# Arduino-Pro-Mini.net
KiCad netlist of a schematic drawn in EAGLE
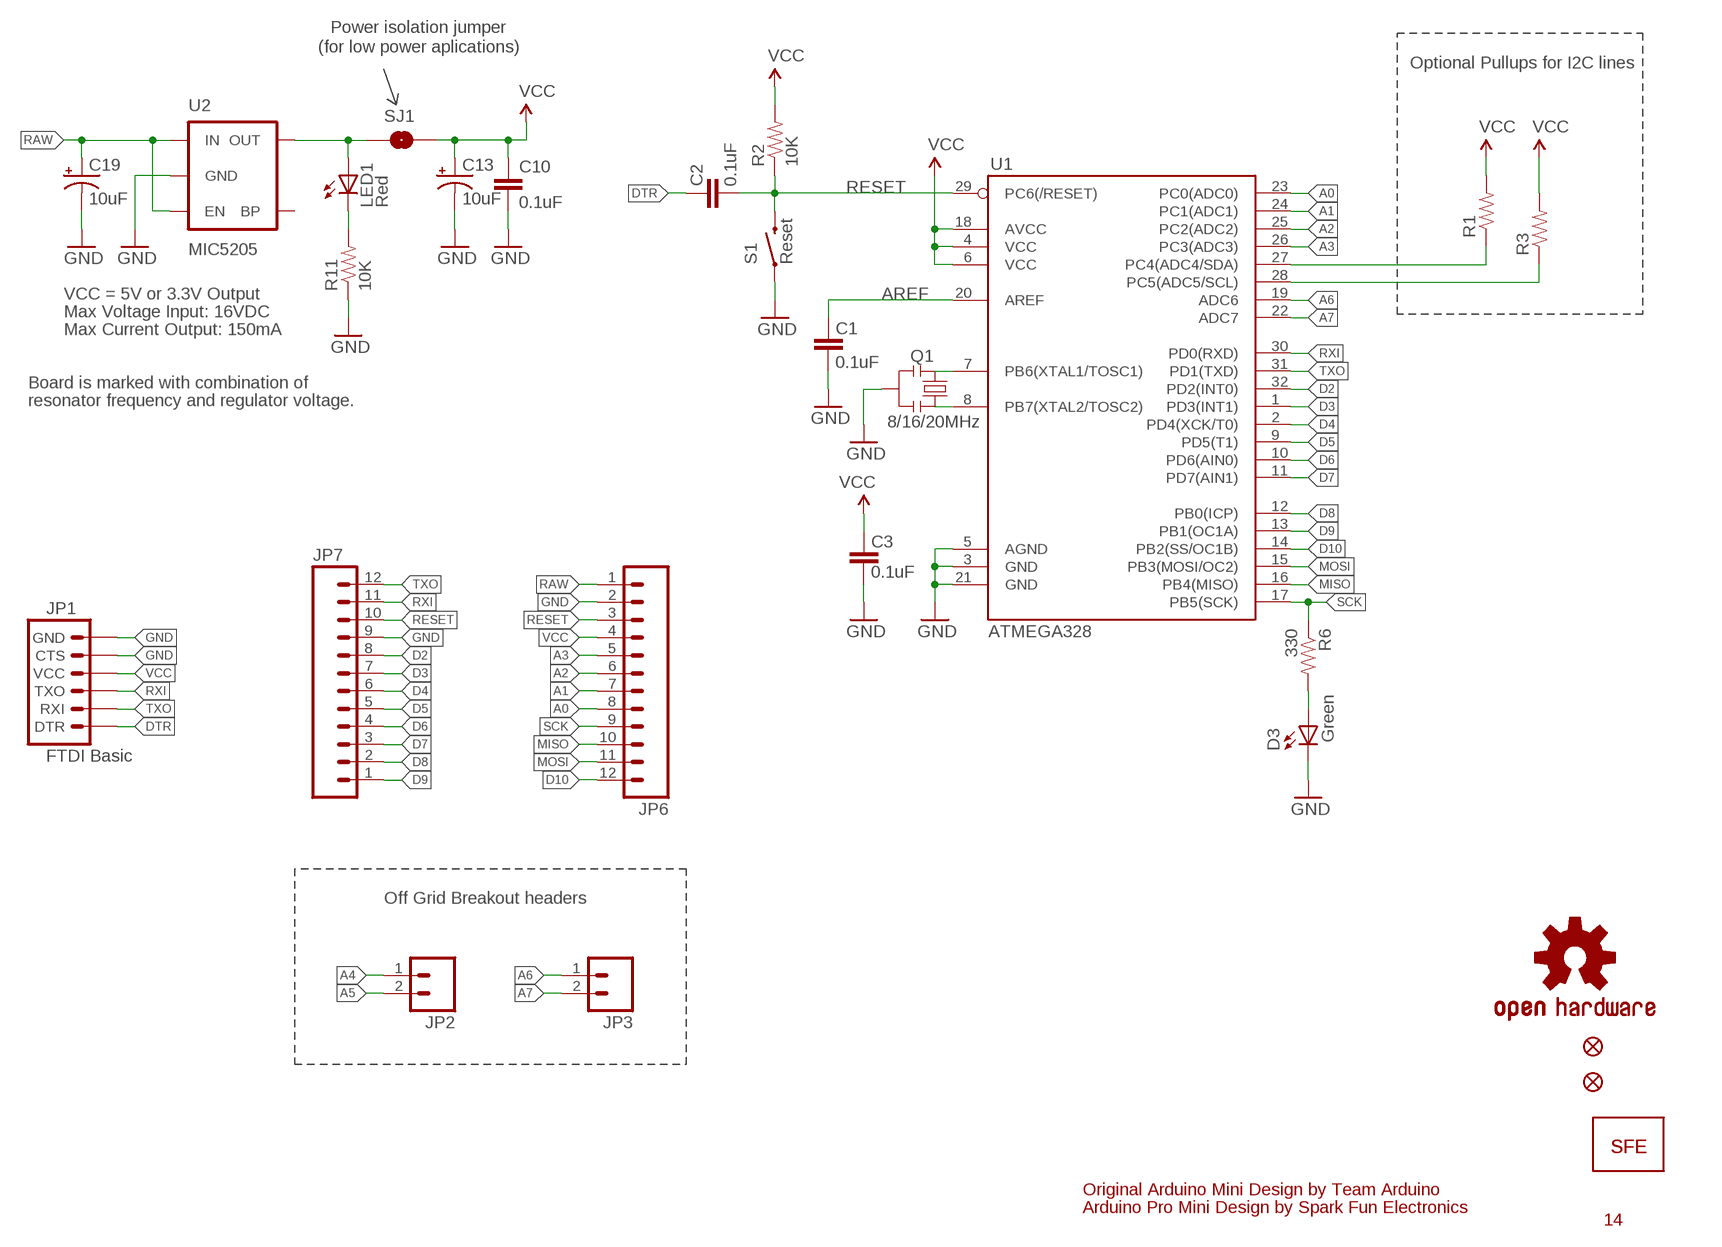
[diagram p0: schematic, sheet 1]

(export (version "E")
  (design (tool "Eeschema 10.0.6"))
  (components
    (comp (ref "C1")
      (value "0.1uF")
      (footprint "eagle-import:0603-CAP")
      (libsource (lib "eagle-import") (part "CAP0603-CAP"))
    )
    (comp (ref "C2")
      (value "0.1uF")
      (footprint "eagle-import:0603-CAP")
      (libsource (lib "eagle-import") (part "CAP0603-CAP"))
    )
    (comp (ref "C3")
      (value "0.1uF")
      (footprint "eagle-import:0603-CAP")
      (libsource (lib "eagle-import") (part "CAP0603-CAP"))
    )
    (comp (ref "C10")
      (value "0.1uF")
      (footprint "eagle-import:0603-CAP")
      (libsource (lib "eagle-import") (part "CAP0603-CAP"))
    )
    (comp (ref "C13")
      (value "10uF")
      (footprint "eagle-import:EIA3216")
      (libsource (lib "eagle-import") (part "CAP_POL1206"))
    )
    (comp (ref "C19")
      (value "10uF")
      (footprint "eagle-import:EIA3216")
      (libsource (lib "eagle-import") (part "CAP_POL1206"))
    )
    (comp (ref "D3")
      (value "Green")
      (footprint "eagle-import:0603-LED-ALT1")
      (libsource (lib "eagle-import") (part "LED"))
    )
    (comp (ref "JP1")
      (value "FTDI Basic")
      (footprint "eagle-import:1X06")
      (libsource (lib "eagle-import") (part "ARDUINO_SERIAL_PROGRAMPTH"))
    )
    (comp (ref "JP2")
      (value "M02PTH")
      (footprint "eagle-import:1X02")
      (libsource (lib "eagle-import") (part "M02PTH"))
    )
    (comp (ref "JP3")
      (value "M02PTH")
      (footprint "eagle-import:1X02")
      (libsource (lib "eagle-import") (part "M02PTH"))
    )
    (comp (ref "JP5")
      (value "FIDUCIALUFIDUCIAL")
      (footprint "eagle-import:MICRO-FIDUCIAL")
      (libsource (lib "eagle-import") (part "FIDUCIALUFIDUCIAL"))
    )
    (comp (ref "JP6")
      (value "M12PTH")
      (footprint "eagle-import:1X12")
      (libsource (lib "eagle-import") (part "M12PTH"))
    )
    (comp (ref "JP7")
      (value "M12PTH")
      (footprint "eagle-import:1X12")
      (libsource (lib "eagle-import") (part "M12PTH"))
    )
    (comp (ref "JP8")
      (value "FIDUCIALUFIDUCIAL")
      (footprint "eagle-import:MICRO-FIDUCIAL")
      (libsource (lib "eagle-import") (part "FIDUCIALUFIDUCIAL"))
    )
    (comp (ref "LED1")
      (value "Red")
      (footprint "eagle-import:0603-LED-ALT1")
      (libsource (lib "eagle-import") (part "LED"))
    )
    (comp (ref "Q1")
      (value "8/16/20MHz")
      (footprint "eagle-import:RESONATOR-SMD-1_1")
      (libsource (lib "eagle-import") (part "RESONATOR1{colon}1"))
    )
    (comp (ref "R1")
      (value "RESISTOR0603-RES")
      (footprint "eagle-import:0603-RES")
      (libsource (lib "eagle-import") (part "RESISTOR0603-RES"))
    )
    (comp (ref "R2")
      (value "10K")
      (footprint "eagle-import:0603-RES")
      (libsource (lib "eagle-import") (part "RESISTOR0603-RES"))
    )
    (comp (ref "R3")
      (value "RESISTOR0603-RES")
      (footprint "eagle-import:0603-RES")
      (libsource (lib "eagle-import") (part "RESISTOR0603-RES"))
    )
    (comp (ref "R6")
      (value "330")
      (footprint "eagle-import:0603-RES")
      (libsource (lib "eagle-import") (part "RESISTOR0603-RES"))
    )
    (comp (ref "R11")
      (value "10K")
      (footprint "eagle-import:0603-RES")
      (libsource (lib "eagle-import") (part "RESISTOR0603-RES"))
    )
    (comp (ref "S1")
      (value "Reset")
      (footprint "eagle-import:TACTILE-SWITCH-SMD-ALT01")
      (libsource (lib "eagle-import") (part "SWITCH-MOMENTARY-2SMD-ALT01"))
    )
    (comp (ref "SJ1")
      (value "SOLDERJUMPERNC")
      (footprint "eagle-import:SJ_2S")
      (libsource (lib "eagle-import") (part "SOLDERJUMPERNC"))
    )
    (comp (ref "U$1")
      (value "LOGO-SFESK")
      (footprint "eagle-import:SFE-LOGO-FLAME")
      (libsource (lib "eagle-import") (part "LOGO-SFESK"))
    )
    (comp (ref "U$3")
      (value "OSHW-LOGOS")
      (footprint "eagle-import:OSHW-LOGO-S")
      (libsource (lib "eagle-import") (part "OSHW-LOGOS"))
    )
    (comp (ref "U$11")
      (value "LOGO-SFENEW")
      (footprint "eagle-import:SFE-NEW-WEBLOGO")
      (libsource (lib "eagle-import") (part "LOGO-SFENEW"))
    )
    (comp (ref "U1")
      (value "ATMEGA328")
      (footprint "eagle-import:TQFP32-08")
      (libsource (lib "eagle-import") (part "ATMEGA168"))
    )
    (comp (ref "U2")
      (value "MIC5205")
      (footprint "eagle-import:SOT23-5")
      (libsource (lib "eagle-import") (part "V_REG_LDOSMD"))
    )
  )
  (nets
    (net (code "1") (name "/AREF") (class "Default")
      (node (ref "C1") (pin "2") (pinfunction "2_2") (pintype "passive"))
      (node (ref "U1") (pin "20") (pinfunction "AREF_20") (pintype "bidirectional"))
    )
    (net (code "2") (name "A0") (class "Default")
      (node (ref "JP6") (pin "8") (pinfunction "8_8") (pintype "passive"))
      (node (ref "U1") (pin "23") (pinfunction "PC0(ADC0)_23") (pintype "bidirectional"))
    )
    (net (code "3") (name "A1") (class "Default")
      (node (ref "JP6") (pin "7") (pinfunction "7_7") (pintype "passive"))
      (node (ref "U1") (pin "24") (pinfunction "PC1(ADC1)_24") (pintype "bidirectional"))
    )
    (net (code "4") (name "A2") (class "Default")
      (node (ref "JP6") (pin "6") (pinfunction "6_6") (pintype "passive"))
      (node (ref "U1") (pin "25") (pinfunction "PC2(ADC2)_25") (pintype "bidirectional"))
    )
    (net (code "5") (name "A3") (class "Default")
      (node (ref "JP6") (pin "5") (pinfunction "5_5") (pintype "passive"))
      (node (ref "U1") (pin "26") (pinfunction "PC3(ADC3)_26") (pintype "bidirectional"))
    )
    (net (code "6") (name "A4") (class "Default")
      (node (ref "JP2") (pin "1") (pinfunction "1_1") (pintype "passive"))
      (node (ref "R1") (pin "1") (pinfunction "1_1") (pintype "passive"))
      (node (ref "U1") (pin "27") (pinfunction "PC4(ADC4/SDA)_27") (pintype "bidirectional"))
    )
    (net (code "7") (name "A5") (class "Default")
      (node (ref "JP2") (pin "2") (pinfunction "2_2") (pintype "passive"))
      (node (ref "R3") (pin "1") (pinfunction "1_1") (pintype "passive"))
      (node (ref "U1") (pin "28") (pinfunction "PC5(ADC5/SCL)_28") (pintype "bidirectional"))
    )
    (net (code "8") (name "A6") (class "Default")
      (node (ref "JP3") (pin "1") (pinfunction "1_1") (pintype "passive"))
      (node (ref "U1") (pin "19") (pinfunction "ADC6_19") (pintype "bidirectional"))
    )
    (net (code "9") (name "A7") (class "Default")
      (node (ref "JP3") (pin "2") (pinfunction "2_2") (pintype "passive"))
      (node (ref "U1") (pin "22") (pinfunction "ADC7_22") (pintype "bidirectional"))
    )
    (net (code "10") (name "D2") (class "Default")
      (node (ref "JP7") (pin "8") (pinfunction "8_8") (pintype "passive"))
      (node (ref "U1") (pin "32") (pinfunction "PD2(INT0)_32") (pintype "bidirectional"))
    )
    (net (code "11") (name "D3") (class "Default")
      (node (ref "JP7") (pin "7") (pinfunction "7_7") (pintype "passive"))
      (node (ref "U1") (pin "1") (pinfunction "PD3(INT1)_1") (pintype "bidirectional"))
    )
    (net (code "12") (name "D4") (class "Default")
      (node (ref "JP7") (pin "6") (pinfunction "6_6") (pintype "passive"))
      (node (ref "U1") (pin "2") (pinfunction "PD4(XCK/T0)_2") (pintype "bidirectional"))
    )
    (net (code "13") (name "D5") (class "Default")
      (node (ref "JP7") (pin "5") (pinfunction "5_5") (pintype "passive"))
      (node (ref "U1") (pin "9") (pinfunction "PD5(T1)_9") (pintype "bidirectional"))
    )
    (net (code "14") (name "D6") (class "Default")
      (node (ref "JP7") (pin "4") (pinfunction "4_4") (pintype "passive"))
      (node (ref "U1") (pin "10") (pinfunction "PD6(AIN0)_10") (pintype "bidirectional"))
    )
    (net (code "15") (name "D7") (class "Default")
      (node (ref "JP7") (pin "3") (pinfunction "3_3") (pintype "passive"))
      (node (ref "U1") (pin "11") (pinfunction "PD7(AIN1)_11") (pintype "bidirectional"))
    )
    (net (code "16") (name "D8") (class "Default")
      (node (ref "JP7") (pin "2") (pinfunction "2_2") (pintype "passive"))
      (node (ref "U1") (pin "12") (pinfunction "PB0(ICP)_12") (pintype "bidirectional"))
    )
    (net (code "17") (name "D9") (class "Default")
      (node (ref "JP7") (pin "1") (pinfunction "1_1") (pintype "passive"))
      (node (ref "U1") (pin "13") (pinfunction "PB1(OC1A)_13") (pintype "bidirectional"))
    )
    (net (code "18") (name "D10") (class "Default")
      (node (ref "JP6") (pin "12") (pinfunction "12_12") (pintype "passive"))
      (node (ref "U1") (pin "14") (pinfunction "PB2(SS/OC1B)_14") (pintype "bidirectional"))
    )
    (net (code "19") (name "DTR") (class "Default")
      (node (ref "C2") (pin "2") (pinfunction "2_2") (pintype "passive"))
      (node (ref "JP1") (pin "1") (pinfunction "DTR_1") (pintype "passive"))
    )
    (net (code "20") (name "GND") (class "Default")
      (node (ref "C1") (pin "1") (pinfunction "1_1") (pintype "passive"))
      (node (ref "C10") (pin "2") (pinfunction "2_2") (pintype "passive"))
      (node (ref "C13") (pin "C") (pinfunction "-_C") (pintype "passive"))
      (node (ref "C19") (pin "C") (pinfunction "-_C") (pintype "passive"))
      (node (ref "C3") (pin "1") (pinfunction "1_1") (pintype "passive"))
      (node (ref "D3") (pin "C") (pinfunction "C_C") (pintype "passive"))
      (node (ref "JP1") (pin "5") (pinfunction "CTS_5") (pintype "passive"))
      (node (ref "JP1") (pin "6") (pinfunction "GND_6") (pintype "passive"))
      (node (ref "JP6") (pin "2") (pinfunction "2_2") (pintype "passive"))
      (node (ref "JP7") (pin "9") (pinfunction "9_9") (pintype "passive"))
      (node (ref "Q1") (pin "2") (pinfunction "2_2") (pintype "passive"))
      (node (ref "R11") (pin "1") (pinfunction "1_1") (pintype "passive"))
      (node (ref "S1") (pin "1") (pinfunction "1_1") (pintype "passive"))
      (node (ref "S1") (pin "2") (pinfunction "1_2") (pintype "passive"))
      (node (ref "U1") (pin "21") (pinfunction "GND_21") (pintype "bidirectional"))
      (node (ref "U1") (pin "3") (pinfunction "GND_3") (pintype "bidirectional"))
      (node (ref "U1") (pin "5") (pinfunction "AGND_5") (pintype "bidirectional"))
      (node (ref "U2") (pin "2") (pinfunction "GND_2") (pintype "input"))
    )
    (net (code "21") (name "MISO") (class "Default")
      (node (ref "JP6") (pin "10") (pinfunction "10_10") (pintype "passive"))
      (node (ref "U1") (pin "16") (pinfunction "PB4(MISO)_16") (pintype "bidirectional"))
    )
    (net (code "22") (name "MOSI") (class "Default")
      (node (ref "JP6") (pin "11") (pinfunction "11_11") (pintype "passive"))
      (node (ref "U1") (pin "15") (pinfunction "PB3(MOSI/OC2)_15") (pintype "bidirectional"))
    )
    (net (code "23") (name "Net-(D3-PadA)") (class "Default")
      (node (ref "D3") (pin "A") (pinfunction "A_A") (pintype "passive"))
      (node (ref "R6") (pin "2") (pinfunction "2_2") (pintype "passive"))
    )
    (net (code "24") (name "Net-(LED1-PadC)") (class "Default")
      (node (ref "LED1") (pin "C") (pinfunction "C_C") (pintype "passive"))
      (node (ref "R11") (pin "2") (pinfunction "2_2") (pintype "passive"))
    )
    (net (code "25") (name "Net-(U1-PB6(XTAL1{slash}TOSC1))") (class "Default")
      (node (ref "Q1") (pin "1") (pinfunction "1_1") (pintype "passive"))
      (node (ref "U1") (pin "7") (pinfunction "PB6(XTAL1/TOSC1)_7") (pintype "bidirectional"))
    )
    (net (code "26") (name "Net-(U1-PB7(XTAL2{slash}TOSC2))") (class "Default")
      (node (ref "Q1") (pin "3") (pinfunction "3_3") (pintype "passive"))
      (node (ref "U1") (pin "8") (pinfunction "PB7(XTAL2/TOSC2)_8") (pintype "bidirectional"))
    )
    (net (code "27") (name "Net-(U2-OUT)") (class "Default")
      (node (ref "LED1") (pin "A") (pinfunction "A_A") (pintype "passive"))
      (node (ref "SJ1") (pin "1") (pinfunction "1_1") (pintype "passive"))
      (node (ref "U2") (pin "5") (pinfunction "OUT_5") (pintype "passive"))
    )
    (net (code "28") (name "RAW") (class "Default")
      (node (ref "C19") (pin "A") (pinfunction "+_A") (pintype "passive"))
      (node (ref "JP6") (pin "1") (pinfunction "1_1") (pintype "passive"))
      (node (ref "U2") (pin "1") (pinfunction "IN_1") (pintype "input"))
      (node (ref "U2") (pin "3") (pinfunction "EN_3") (pintype "input"))
    )
    (net (code "29") (name "RESET") (class "Default")
      (node (ref "C2") (pin "1") (pinfunction "1_1") (pintype "passive"))
      (node (ref "JP6") (pin "3") (pinfunction "3_3") (pintype "passive"))
      (node (ref "JP7") (pin "10") (pinfunction "10_10") (pintype "passive"))
      (node (ref "R2") (pin "1") (pinfunction "1_1") (pintype "passive"))
      (node (ref "S1") (pin "3") (pinfunction "2_3") (pintype "passive"))
      (node (ref "S1") (pin "4") (pinfunction "2_4") (pintype "passive"))
      (node (ref "U1") (pin "29") (pinfunction "PC6(/RESET)_29") (pintype "bidirectional"))
    )
    (net (code "30") (name "RXI") (class "Default")
      (node (ref "JP1") (pin "3") (pinfunction "TXO_3") (pintype "passive"))
      (node (ref "JP7") (pin "11") (pinfunction "11_11") (pintype "passive"))
      (node (ref "U1") (pin "30") (pinfunction "PD0(RXD)_30") (pintype "bidirectional"))
    )
    (net (code "31") (name "SCK") (class "Default")
      (node (ref "JP6") (pin "9") (pinfunction "9_9") (pintype "passive"))
      (node (ref "R6") (pin "1") (pinfunction "1_1") (pintype "passive"))
      (node (ref "U1") (pin "17") (pinfunction "PB5(SCK)_17") (pintype "bidirectional"))
    )
    (net (code "32") (name "TXO") (class "Default")
      (node (ref "JP1") (pin "2") (pinfunction "RXI_2") (pintype "passive"))
      (node (ref "JP7") (pin "12") (pinfunction "12_12") (pintype "passive"))
      (node (ref "U1") (pin "31") (pinfunction "PD1(TXD)_31") (pintype "bidirectional"))
    )
    (net (code "33") (name "VCC") (class "Default")
      (node (ref "C10") (pin "1") (pinfunction "1_1") (pintype "passive"))
      (node (ref "C13") (pin "A") (pinfunction "+_A") (pintype "passive"))
      (node (ref "C3") (pin "2") (pinfunction "2_2") (pintype "passive"))
      (node (ref "JP1") (pin "4") (pinfunction "VCC_4") (pintype "passive"))
      (node (ref "JP6") (pin "4") (pinfunction "4_4") (pintype "passive"))
      (node (ref "R1") (pin "2") (pinfunction "2_2") (pintype "passive"))
      (node (ref "R2") (pin "2") (pinfunction "2_2") (pintype "passive"))
      (node (ref "R3") (pin "2") (pinfunction "2_2") (pintype "passive"))
      (node (ref "SJ1") (pin "2") (pinfunction "2_2") (pintype "passive"))
      (node (ref "U1") (pin "18") (pinfunction "AVCC_18") (pintype "bidirectional"))
      (node (ref "U1") (pin "4") (pinfunction "VCC_4") (pintype "bidirectional"))
      (node (ref "U1") (pin "6") (pinfunction "VCC_6") (pintype "bidirectional"))
    )
    (net (code "34") (name "unconnected-(U2-BP-Pad4)") (class "Default")
      (node (ref "U2") (pin "4") (pinfunction "BP_4") (pintype "input"))
    )
  )
)
